# UBC-Thunderbots_PCB_Power__power-v3_1_pc.net
KiCad netlist of a schematic drawn in Altium Designer
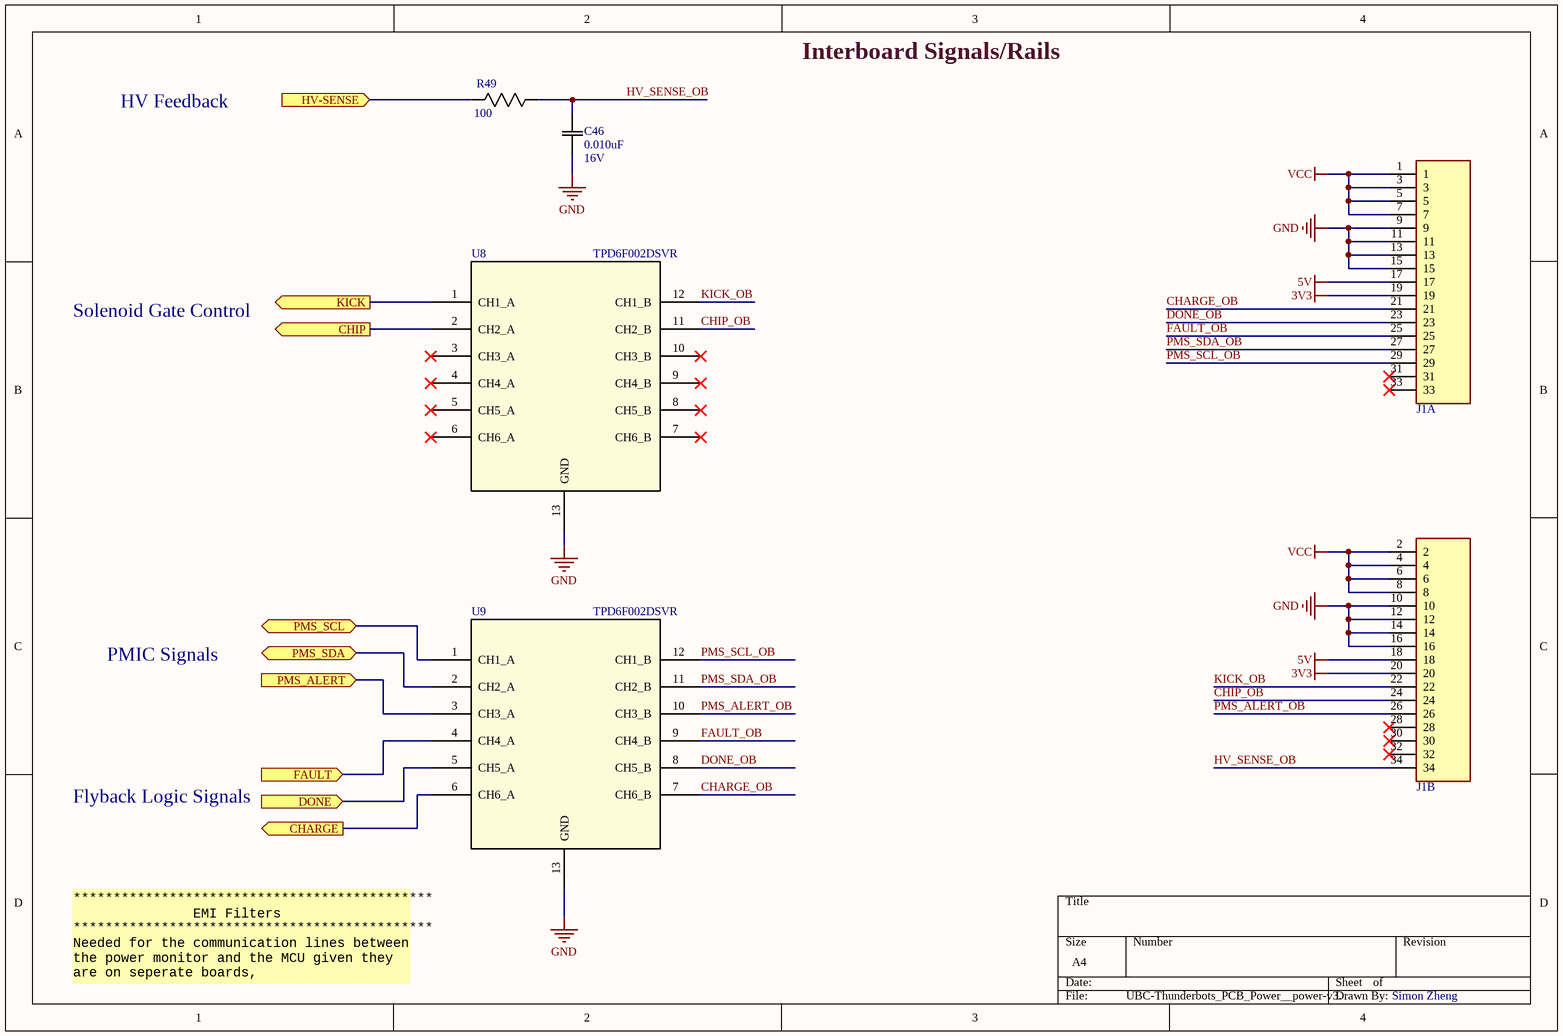
[diagram p0: UBC-Thunderbots_PCB_Power__power-v3.1_pcb__communication.SchDoc]

(export (version "E")
  (design (tool "Eeschema 10.0.6"))
  (components
    (comp (ref "C46")
      (value "0.010uF")
      (footprint "0805")
      (description "CAP CER 0.010UF 16V X5R 0603/0805")
      (fields (field (name "TOLERANCE") "10%") (field (name "RATING") "16V"))
      (libsource (lib "AltiumLibraries") (part "CAP 0.010uF 16V"))
    )
    (comp (ref "J1")
      (value "0.1\" Header Female 34")
      (footprint "SAMTEC_ESQ-117-12-L-D")
      (description "Female Header THRU 34POS 2ROW 0.1\" (2.54mm) pitch")
      (libsource (lib "AltiumLibraries") (part "CN HDR 34POS 2x17"))
    )
    (comp (ref "R49")
      (value "100")
      (footprint "0805")
      (description "RES SMD 100 OHM 5% 1/8W 0805")
      (fields (field (name "TOLERANCE") "5%"))
      (libsource (lib "AltiumLibraries") (part "RES 100.0 1/8W"))
    )
    (comp (ref "U8")
      (value "TPD6F002DSVR")
      (footprint "PSON50P140X80_HS-13N")
      (description "6-Channel EMI Filter for Display Interface")
      (fields
        (field (name "MANUFACTURER") "Texas Instruments")
        (field (name "GENERIC_PART_NUMBER") "TPD6F002")
        (field (name "COPYRIGHT") "Copyright (C) 2018 Accelerated Designs. All rights reserved")
      )
      (libsource (lib "AltiumLibraries") (part "EMI FILTER TPD6F002DSVR"))
    )
    (comp (ref "U9")
      (value "TPD6F002DSVR")
      (footprint "PSON50P140X80_HS-13N")
      (description "6-Channel EMI Filter for Display Interface")
      (fields
        (field (name "MANUFACTURER") "Texas Instruments")
        (field (name "GENERIC_PART_NUMBER") "TPD6F002")
        (field (name "COPYRIGHT") "Copyright (C) 2018 Accelerated Designs. All rights reserved")
      )
      (libsource (lib "AltiumLibraries") (part "EMI FILTER TPD6F002DSVR"))
    )
  )
  (nets
    (net (code "1") (name "/CHARGE") (class "Default")
      (node (ref "U9") (pin "6") (pinfunction "CH6_A_6") (pintype "passive"))
    )
    (net (code "2") (name "/CHARGE_OB") (class "Default")
      (node (ref "J1") (pin "21") (pinfunction "21_21") (pintype "passive"))
      (node (ref "U9") (pin "7") (pinfunction "CH6_B_7") (pintype "passive"))
    )
    (net (code "3") (name "/CHIP") (class "Default")
      (node (ref "U8") (pin "2") (pinfunction "CH2_A_2") (pintype "passive"))
    )
    (net (code "4") (name "/CHIP_OB") (class "Default")
      (node (ref "J1") (pin "24") (pinfunction "24_24") (pintype "passive"))
      (node (ref "U8") (pin "11") (pinfunction "CH2_B_11") (pintype "passive"))
    )
    (net (code "5") (name "/DONE") (class "Default")
      (node (ref "U9") (pin "5") (pinfunction "CH5_A_5") (pintype "passive"))
    )
    (net (code "6") (name "/DONE_OB") (class "Default")
      (node (ref "J1") (pin "23") (pinfunction "23_23") (pintype "passive"))
      (node (ref "U9") (pin "8") (pinfunction "CH5_B_8") (pintype "passive"))
    )
    (net (code "7") (name "/FAULT") (class "Default")
      (node (ref "U9") (pin "4") (pinfunction "CH4_A_4") (pintype "passive"))
    )
    (net (code "8") (name "/FAULT_OB") (class "Default")
      (node (ref "J1") (pin "25") (pinfunction "25_25") (pintype "passive"))
      (node (ref "U9") (pin "9") (pinfunction "CH4_B_9") (pintype "passive"))
    )
    (net (code "9") (name "/HV-SENSE") (class "Default")
      (node (ref "R49") (pin "2") (pinfunction "R2_2") (pintype "passive"))
    )
    (net (code "10") (name "/HV_SENSE_OB") (class "Default")
      (node (ref "C46") (pin "1") (pinfunction "C1_1") (pintype "passive"))
      (node (ref "J1") (pin "34") (pinfunction "34_34") (pintype "passive"))
      (node (ref "R49") (pin "1") (pinfunction "R1_1") (pintype "passive"))
    )
    (net (code "11") (name "/KICK") (class "Default")
      (node (ref "U8") (pin "1") (pinfunction "CH1_A_1") (pintype "passive"))
    )
    (net (code "12") (name "/KICK_OB") (class "Default")
      (node (ref "J1") (pin "22") (pinfunction "22_22") (pintype "passive"))
      (node (ref "U8") (pin "12") (pinfunction "CH1_B_12") (pintype "passive"))
    )
    (net (code "13") (name "/PMS_ALERT") (class "Default")
      (node (ref "U9") (pin "3") (pinfunction "CH3_A_3") (pintype "passive"))
    )
    (net (code "14") (name "/PMS_ALERT_OB") (class "Default")
      (node (ref "J1") (pin "26") (pinfunction "26_26") (pintype "passive"))
      (node (ref "U9") (pin "10") (pinfunction "CH3_B_10") (pintype "passive"))
    )
    (net (code "15") (name "/PMS_SCL") (class "Default")
      (node (ref "U9") (pin "1") (pinfunction "CH1_A_1") (pintype "passive"))
    )
    (net (code "16") (name "/PMS_SCL_OB") (class "Default")
      (node (ref "J1") (pin "29") (pinfunction "29_29") (pintype "passive"))
      (node (ref "U9") (pin "12") (pinfunction "CH1_B_12") (pintype "passive"))
    )
    (net (code "17") (name "/PMS_SDA") (class "Default")
      (node (ref "U9") (pin "2") (pinfunction "CH2_A_2") (pintype "passive"))
    )
    (net (code "18") (name "/PMS_SDA_OB") (class "Default")
      (node (ref "J1") (pin "27") (pinfunction "27_27") (pintype "passive"))
      (node (ref "U9") (pin "11") (pinfunction "CH2_B_11") (pintype "passive"))
    )
    (net (code "19") (name "3V3") (class "Default")
      (node (ref "J1") (pin "19") (pinfunction "19_19") (pintype "passive"))
      (node (ref "J1") (pin "20") (pinfunction "20_20") (pintype "passive"))
    )
    (net (code "20") (name "5V") (class "Default")
      (node (ref "J1") (pin "17") (pinfunction "17_17") (pintype "passive"))
      (node (ref "J1") (pin "18") (pinfunction "18_18") (pintype "passive"))
    )
    (net (code "21") (name "GND") (class "Default")
      (node (ref "C46") (pin "2") (pinfunction "C2_2") (pintype "passive"))
      (node (ref "J1") (pin "10") (pinfunction "10_10") (pintype "passive"))
      (node (ref "J1") (pin "11") (pinfunction "11_11") (pintype "passive"))
      (node (ref "J1") (pin "12") (pinfunction "12_12") (pintype "passive"))
      (node (ref "J1") (pin "13") (pinfunction "13_13") (pintype "passive"))
      (node (ref "J1") (pin "14") (pinfunction "14_14") (pintype "passive"))
      (node (ref "J1") (pin "15") (pinfunction "15_15") (pintype "passive"))
      (node (ref "J1") (pin "16") (pinfunction "16_16") (pintype "passive"))
      (node (ref "J1") (pin "9") (pinfunction "9_9") (pintype "passive"))
      (node (ref "U8") (pin "13") (pinfunction "GND_13") (pintype "passive"))
      (node (ref "U9") (pin "13") (pinfunction "GND_13") (pintype "passive"))
    )
    (net (code "22") (name "VCC") (class "Default")
      (node (ref "J1") (pin "1") (pinfunction "1_1") (pintype "passive"))
      (node (ref "J1") (pin "2") (pinfunction "2_2") (pintype "passive"))
      (node (ref "J1") (pin "3") (pinfunction "3_3") (pintype "passive"))
      (node (ref "J1") (pin "4") (pinfunction "4_4") (pintype "passive"))
      (node (ref "J1") (pin "5") (pinfunction "5_5") (pintype "passive"))
      (node (ref "J1") (pin "6") (pinfunction "6_6") (pintype "passive"))
      (node (ref "J1") (pin "7") (pinfunction "7_7") (pintype "passive"))
      (node (ref "J1") (pin "8") (pinfunction "8_8") (pintype "passive"))
    )
    (net (code "23") (name "unconnected-(J1-Pad28)") (class "Default")
      (node (ref "J1") (pin "28") (pinfunction "28_28") (pintype "passive+no_connect"))
    )
    (net (code "24") (name "unconnected-(J1-Pad30)") (class "Default")
      (node (ref "J1") (pin "30") (pinfunction "30_30") (pintype "passive+no_connect"))
    )
    (net (code "25") (name "unconnected-(J1-Pad31)") (class "Default")
      (node (ref "J1") (pin "31") (pinfunction "31_31") (pintype "passive+no_connect"))
    )
    (net (code "26") (name "unconnected-(J1-Pad32)") (class "Default")
      (node (ref "J1") (pin "32") (pinfunction "32_32") (pintype "passive+no_connect"))
    )
    (net (code "27") (name "unconnected-(J1-Pad33)") (class "Default")
      (node (ref "J1") (pin "33") (pinfunction "33_33") (pintype "passive+no_connect"))
    )
    (net (code "28") (name "unconnected-(U8-CH3_A-Pad3)") (class "Default")
      (node (ref "U8") (pin "3") (pinfunction "CH3_A_3") (pintype "passive+no_connect"))
    )
    (net (code "29") (name "unconnected-(U8-CH3_B-Pad10)") (class "Default")
      (node (ref "U8") (pin "10") (pinfunction "CH3_B_10") (pintype "passive+no_connect"))
    )
    (net (code "30") (name "unconnected-(U8-CH4_A-Pad4)") (class "Default")
      (node (ref "U8") (pin "4") (pinfunction "CH4_A_4") (pintype "passive+no_connect"))
    )
    (net (code "31") (name "unconnected-(U8-CH4_B-Pad9)") (class "Default")
      (node (ref "U8") (pin "9") (pinfunction "CH4_B_9") (pintype "passive+no_connect"))
    )
    (net (code "32") (name "unconnected-(U8-CH5_A-Pad5)") (class "Default")
      (node (ref "U8") (pin "5") (pinfunction "CH5_A_5") (pintype "passive+no_connect"))
    )
    (net (code "33") (name "unconnected-(U8-CH5_B-Pad8)") (class "Default")
      (node (ref "U8") (pin "8") (pinfunction "CH5_B_8") (pintype "passive+no_connect"))
    )
    (net (code "34") (name "unconnected-(U8-CH6_A-Pad6)") (class "Default")
      (node (ref "U8") (pin "6") (pinfunction "CH6_A_6") (pintype "passive+no_connect"))
    )
    (net (code "35") (name "unconnected-(U8-CH6_B-Pad7)") (class "Default")
      (node (ref "U8") (pin "7") (pinfunction "CH6_B_7") (pintype "passive+no_connect"))
    )
  )
)
